# STM32.net
KiCad netlist of a schematic drawn in Altium Designer
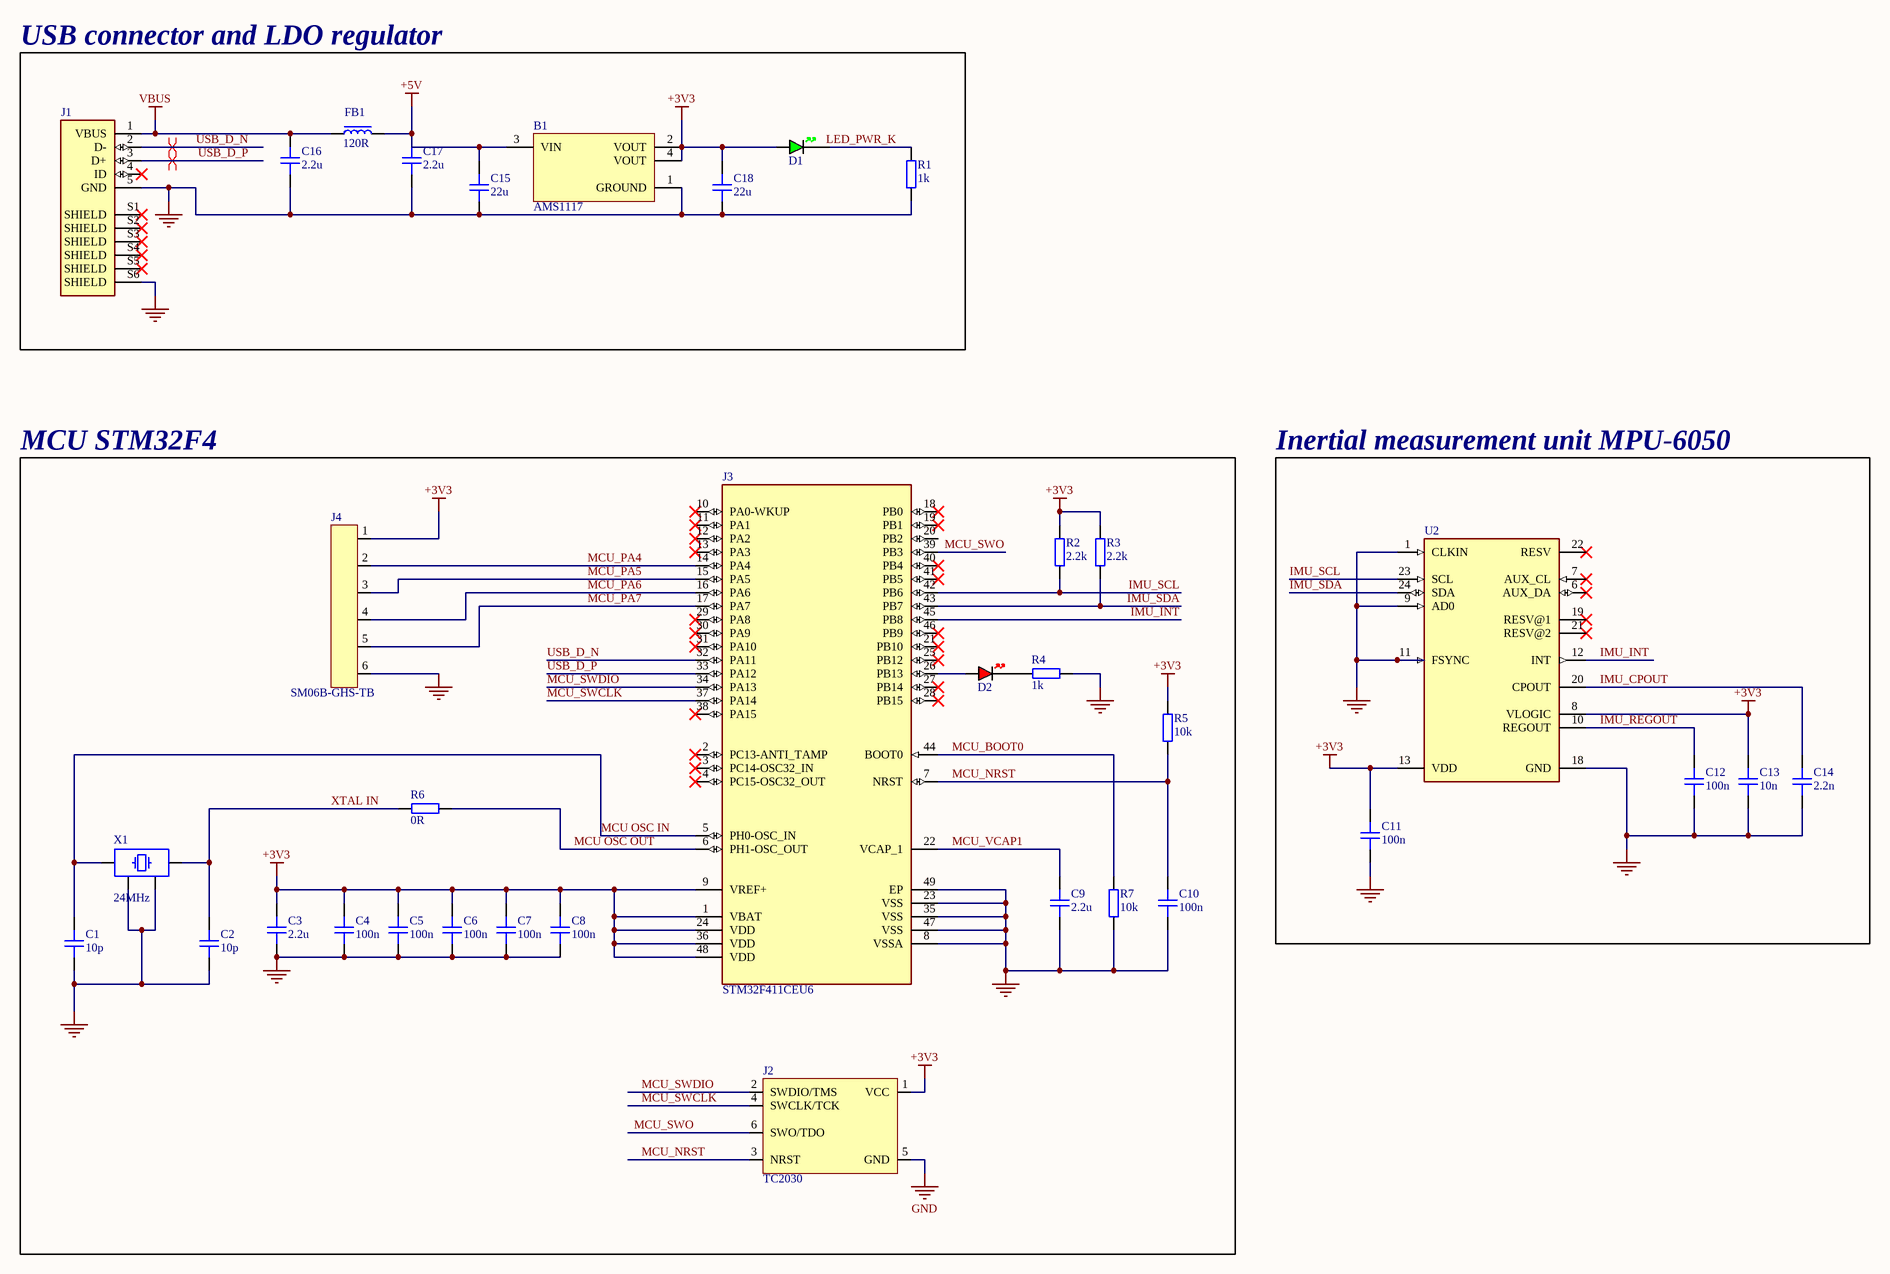
[diagram p0: STM32.SchDoc]

(export (version "E")
  (design (tool "Eeschema 10.0.6"))
  (components
    (comp (ref "B1")
      (value "AMS1117")
      (footprint "SOT229P700X180-4N")
      (description "1117")
      (libsource (lib "AMS1117") (part "AMS1117"))
    )
    (comp (ref "C1")
      (value "10p")
      (footprint "CAP_0603")
      (description "Capacitor SMD 0603")
      (libsource (lib "Schematic-Lib-PhilsLab") (part "CAP_0603"))
    )
    (comp (ref "C2")
      (value "10p")
      (footprint "CAP_0603")
      (description "Capacitor SMD 0603")
      (libsource (lib "Schematic-Lib-PhilsLab") (part "CAP_0603"))
    )
    (comp (ref "C3")
      (value "2.2u")
      (footprint "CAP_0603")
      (description "Capacitor SMD 0603")
      (libsource (lib "Schematic-Lib-PhilsLab") (part "CAP_0603"))
    )
    (comp (ref "C4")
      (value "100n")
      (footprint "CAP_0402")
      (description "Capacitor SMD 0402")
      (libsource (lib "Schematic-Lib-PhilsLab") (part "CAP_0402"))
    )
    (comp (ref "C5")
      (value "100n")
      (footprint "CAP_0402")
      (description "Capacitor SMD 0402")
      (libsource (lib "Schematic-Lib-PhilsLab") (part "CAP_0402"))
    )
    (comp (ref "C6")
      (value "100n")
      (footprint "CAP_0402")
      (description "Capacitor SMD 0402")
      (libsource (lib "Schematic-Lib-PhilsLab") (part "CAP_0402"))
    )
    (comp (ref "C7")
      (value "100n")
      (footprint "CAP_0402")
      (description "Capacitor SMD 0402")
      (libsource (lib "Schematic-Lib-PhilsLab") (part "CAP_0402"))
    )
    (comp (ref "C8")
      (value "100n")
      (footprint "CAP_0402")
      (description "Capacitor SMD 0402")
      (libsource (lib "Schematic-Lib-PhilsLab") (part "CAP_0402"))
    )
    (comp (ref "C9")
      (value "2.2u")
      (footprint "CAP_0603")
      (description "Capacitor SMD 0603")
      (libsource (lib "Schematic-Lib-PhilsLab") (part "CAP_0603"))
    )
    (comp (ref "C10")
      (value "100n")
      (footprint "CAP_0402")
      (description "Capacitor SMD 0402")
      (libsource (lib "Schematic-Lib-PhilsLab") (part "CAP_0402"))
    )
    (comp (ref "C11")
      (value "100n")
      (footprint "CAP_0402")
      (description "Capacitor SMD 0402")
      (libsource (lib "Schematic-Lib-PhilsLab") (part "CAP_0402"))
    )
    (comp (ref "C12")
      (value "100n")
      (footprint "CAP_0402")
      (description "Capacitor SMD 0402")
      (libsource (lib "Schematic-Lib-PhilsLab") (part "CAP_0402"))
    )
    (comp (ref "C13")
      (value "10n")
      (footprint "CAP_0402")
      (description "Capacitor SMD 0402")
      (libsource (lib "Schematic-Lib-PhilsLab") (part "CAP_0402"))
    )
    (comp (ref "C14")
      (value "2.2n")
      (footprint "CAP_0402")
      (description "Capacitor SMD 0402")
      (libsource (lib "Schematic-Lib-PhilsLab") (part "CAP_0402"))
    )
    (comp (ref "C15")
      (value "22u")
      (footprint "CAP_0603")
      (description "Capacitor SMD 0603")
      (libsource (lib "Schematic-Lib-PhilsLab") (part "CAP_0603"))
    )
    (comp (ref "C16")
      (value "2.2u")
      (footprint "CAP_0603")
      (description "Capacitor SMD 0603")
      (libsource (lib "Schematic-Lib-PhilsLab") (part "CAP_0603"))
    )
    (comp (ref "C17")
      (value "2.2u")
      (footprint "CAP_0603")
      (description "Capacitor SMD 0603")
      (libsource (lib "Schematic-Lib-PhilsLab") (part "CAP_0603"))
    )
    (comp (ref "C18")
      (value "22u")
      (footprint "CAP_0603")
      (description "Capacitor SMD 0603")
      (libsource (lib "Schematic-Lib-PhilsLab") (part "CAP_0603"))
    )
    (comp (ref "D1")
      (value "GREEN")
      (footprint "LED_0402_GREEN")
      (description "LED 0402 GREEN SMD")
      (libsource (lib "Schematic-Lib-PhilsLab") (part "LED_0402_GREEN"))
    )
    (comp (ref "D2")
      (value "RED")
      (footprint "LED_0402_RED")
      (description "LED 0402 RED SMD")
      (libsource (lib "Schematic-Lib-PhilsLab") (part "LED_0402_RED"))
    )
    (comp (ref "FB1")
      (value "120R")
      (footprint "FB_0603")
      (description "Ferrite Bead SMD 0603")
      (libsource (lib "Schematic-Lib-PhilsLab") (part "FB_0603"))
    )
    (comp (ref "J1")
      (value "~")
      (footprint "MOLEX_47346-0001")
      (description "USB - micro B USB 2.0 Receptacle Connector 5 Position Surface Mount, Right Angle")
      (fields (field (name "MP") "47346-0001") (field (name "MF") "Molex"))
      (libsource (lib "47346-0001") (part "47346-0001"))
    )
    (comp (ref "J2")
      (value "TC2030")
      (footprint "TC2030-FP")
      (description "Tag-Connect No-Solder SWD Debug Connector DO NOT PLACE")
      (fields (field (name "MANUFACTURER") "Tag-Connect"))
      (libsource (lib "Schematic-Lib-PhilsLab") (part "TC2030"))
    )
    (comp (ref "J3")
      (value "STM32F411CEU6")
      (footprint "QFN50P700X700X60-49N")
      (description "IC MCU 32BIT 512KB FLASH 100LQFP")
      (fields
        (field (name "MANUFACTURER") "STMicroelectronics")
        (field (name "MANUFACTURER PART NUMBER") "STM32F411VET6")
      )
      (libsource (lib "STM32") (part "STM32F411VET6"))
    )
    (comp (ref "J4")
      (value "SM06B-GHS-TB")
      (footprint "SM06B-GHS-TB")
      (description "Header Connector 6 Position 1.25MM Pitch SMD Horizontal JST GH")
      (fields (field (name "MANUFACTURER") "JST"))
      (libsource (lib "Schematic-Lib-PhilsLab") (part "SM06B-GHS-TB"))
    )
    (comp (ref "R1")
      (value "1k")
      (footprint "RES_0402")
      (description "Resistor SMD 0402")
      (libsource (lib "Schematic-Lib-PhilsLab") (part "RES_0402"))
    )
    (comp (ref "R2")
      (value "2.2k")
      (footprint "RES_0402")
      (description "Resistor SMD 0402")
      (libsource (lib "Schematic-Lib-PhilsLab") (part "RES_0402"))
    )
    (comp (ref "R3")
      (value "2.2k")
      (footprint "RES_0402")
      (description "Resistor SMD 0402")
      (libsource (lib "Schematic-Lib-PhilsLab") (part "RES_0402"))
    )
    (comp (ref "R4")
      (value "1k")
      (footprint "RES_0402")
      (description "Resistor SMD 0402")
      (libsource (lib "Schematic-Lib-PhilsLab") (part "RES_0402"))
    )
    (comp (ref "R5")
      (value "10k")
      (footprint "RES_0402")
      (description "Resistor SMD 0402")
      (libsource (lib "Schematic-Lib-PhilsLab") (part "RES_0402"))
    )
    (comp (ref "R6")
      (value "0R")
      (footprint "RES_0402")
      (description "Resistor SMD 0402")
      (libsource (lib "Schematic-Lib-PhilsLab") (part "RES_0402"))
    )
    (comp (ref "R7")
      (value "10k")
      (footprint "RES_0402")
      (description "Resistor SMD 0402")
      (libsource (lib "Schematic-Lib-PhilsLab") (part "RES_0402"))
    )
    (comp (ref "U2")
      (value "~")
      (footprint "QFN50P400X400X95-24N")
      (description "MPU-6050 series Accelerometer, Gyroscope, 3 Axis Sensor Evaluation Board")
      (fields (field (name "MF") "TDK InvenSense") (field (name "MP") "MPU-6050"))
      (libsource (lib "MPU-6050 (1)") (part "MPU-6050"))
    )
    (comp (ref "X1")
      (value "24MHz")
      (footprint "XTAL_3225")
      (description "Crystal SMD 24MHz 10PPM 7pF 3225")
      (fields
        (field (name "MANUFACTURER") "Epson")
        (field (name "MANUFACTURER PART NUMBER") "TSX-3225 24.0000MF15X-AC")
      )
      (libsource (lib "Schematic-Lib-PhilsLab") (part "TSX-3225_24.0000MF15X-AC"))
    )
  )
  (nets
    (net (code "1") (name "+3V3") (class "Default")
      (node (ref "B1") (pin "2") (pinfunction "VOUT_2") (pintype "passive"))
      (node (ref "B1") (pin "4") (pinfunction "VOUT_4") (pintype "passive"))
      (node (ref "C11") (pin "2") (pinfunction "2_2") (pintype "passive"))
      (node (ref "C13") (pin "2") (pinfunction "2_2") (pintype "passive"))
      (node (ref "C18") (pin "2") (pinfunction "2_2") (pintype "passive"))
      (node (ref "C3") (pin "2") (pinfunction "2_2") (pintype "passive"))
      (node (ref "C4") (pin "2") (pinfunction "2_2") (pintype "passive"))
      (node (ref "C5") (pin "2") (pinfunction "2_2") (pintype "passive"))
      (node (ref "C6") (pin "2") (pinfunction "2_2") (pintype "passive"))
      (node (ref "C7") (pin "2") (pinfunction "2_2") (pintype "passive"))
      (node (ref "C8") (pin "2") (pinfunction "2_2") (pintype "passive"))
      (node (ref "D1") (pin "A") (pinfunction "A_A") (pintype "passive"))
      (node (ref "J2") (pin "1") (pinfunction "VCC_1") (pintype "passive"))
      (node (ref "J3") (pin "1") (pinfunction "VBAT_1") (pintype "power_in"))
      (node (ref "J3") (pin "24") (pinfunction "VDD_24") (pintype "power_in"))
      (node (ref "J3") (pin "36") (pinfunction "VDD_36") (pintype "power_in"))
      (node (ref "J3") (pin "48") (pinfunction "VDD_48") (pintype "power_in"))
      (node (ref "J3") (pin "9") (pinfunction "VREF+_9") (pintype "power_in"))
      (node (ref "J4") (pin "1") (pinfunction "1_1") (pintype "passive"))
      (node (ref "R2") (pin "1") (pinfunction "1_1") (pintype "passive"))
      (node (ref "R3") (pin "1") (pinfunction "1_1") (pintype "passive"))
      (node (ref "R5") (pin "1") (pinfunction "1_1") (pintype "passive"))
      (node (ref "U2") (pin "13") (pinfunction "VDD_13") (pintype "power_in"))
      (node (ref "U2") (pin "8") (pinfunction "VLOGIC_8") (pintype "power_in"))
    )
    (net (code "2") (name "+5V") (class "Default")
      (node (ref "B1") (pin "3") (pinfunction "VIN_3") (pintype "passive"))
      (node (ref "C15") (pin "2") (pinfunction "2_2") (pintype "passive"))
      (node (ref "C17") (pin "2") (pinfunction "2_2") (pintype "passive"))
      (node (ref "FB1") (pin "2") (pinfunction "2_2") (pintype "passive"))
    )
    (net (code "3") (name "/IMU_CPOUT") (class "Default")
      (node (ref "C14") (pin "2") (pinfunction "2_2") (pintype "passive"))
      (node (ref "U2") (pin "20") (pinfunction "CPOUT_20") (pintype "passive"))
    )
    (net (code "4") (name "/IMU_INT") (class "Default")
      (node (ref "J3") (pin "45") (pinfunction "PB8_45") (pintype "bidirectional"))
      (node (ref "U2") (pin "12") (pinfunction "INT_12") (pintype "output"))
    )
    (net (code "5") (name "/IMU_REGOUT") (class "Default")
      (node (ref "C12") (pin "2") (pinfunction "2_2") (pintype "passive"))
      (node (ref "U2") (pin "10") (pinfunction "REGOUT_10") (pintype "passive"))
    )
    (net (code "6") (name "/IMU_SCL") (class "Default")
      (node (ref "J3") (pin "42") (pinfunction "PB6_42") (pintype "bidirectional"))
      (node (ref "R2") (pin "2") (pinfunction "2_2") (pintype "passive"))
      (node (ref "U2") (pin "23") (pinfunction "SCL_23") (pintype "input"))
    )
    (net (code "7") (name "/IMU_SDA") (class "Default")
      (node (ref "J3") (pin "43") (pinfunction "PB7_43") (pintype "bidirectional"))
      (node (ref "R3") (pin "2") (pinfunction "2_2") (pintype "passive"))
      (node (ref "U2") (pin "24") (pinfunction "SDA_24") (pintype "bidirectional"))
    )
    (net (code "8") (name "/LED_PWR_K") (class "Default")
      (node (ref "D1") (pin "K") (pinfunction "K_K") (pintype "passive"))
      (node (ref "R1") (pin "2") (pinfunction "2_2") (pintype "passive"))
    )
    (net (code "9") (name "/MCU OSC IN") (class "Default")
      (node (ref "C1") (pin "2") (pinfunction "2_2") (pintype "passive"))
      (node (ref "J3") (pin "5") (pinfunction "PH0-OSC_IN_5") (pintype "bidirectional"))
      (node (ref "X1") (pin "1") (pinfunction "1_1") (pintype "passive"))
    )
    (net (code "10") (name "/MCU OSC OUT") (class "Default")
      (node (ref "J3") (pin "6") (pinfunction "PH1-OSC_OUT_6") (pintype "bidirectional"))
      (node (ref "R6") (pin "2") (pinfunction "2_2") (pintype "passive"))
    )
    (net (code "11") (name "/MCU_BOOT0") (class "Default")
      (node (ref "J3") (pin "44") (pinfunction "BOOT0_44") (pintype "input"))
      (node (ref "R7") (pin "1") (pinfunction "1_1") (pintype "passive"))
    )
    (net (code "12") (name "/MCU_NRST") (class "Default")
      (node (ref "C10") (pin "2") (pinfunction "2_2") (pintype "passive"))
      (node (ref "J2") (pin "3") (pinfunction "NRST_3") (pintype "passive"))
      (node (ref "J3") (pin "7") (pinfunction "NRST_7") (pintype "bidirectional"))
      (node (ref "R5") (pin "2") (pinfunction "2_2") (pintype "passive"))
    )
    (net (code "13") (name "/MCU_PA4") (class "Default")
      (node (ref "J3") (pin "14") (pinfunction "PA4_14") (pintype "bidirectional"))
      (node (ref "J4") (pin "2") (pinfunction "2_2") (pintype "passive"))
    )
    (net (code "14") (name "/MCU_PA5") (class "Default")
      (node (ref "J3") (pin "15") (pinfunction "PA5_15") (pintype "bidirectional"))
      (node (ref "J4") (pin "3") (pinfunction "3_3") (pintype "passive"))
    )
    (net (code "15") (name "/MCU_PA6") (class "Default")
      (node (ref "J3") (pin "16") (pinfunction "PA6_16") (pintype "bidirectional"))
      (node (ref "J4") (pin "4") (pinfunction "4_4") (pintype "passive"))
    )
    (net (code "16") (name "/MCU_PA7") (class "Default")
      (node (ref "J3") (pin "17") (pinfunction "PA7_17") (pintype "bidirectional"))
      (node (ref "J4") (pin "5") (pinfunction "5_5") (pintype "passive"))
    )
    (net (code "17") (name "/MCU_SWCLK") (class "Default")
      (node (ref "J2") (pin "4") (pinfunction "SWCLK/TCK_4") (pintype "passive"))
      (node (ref "J3") (pin "37") (pinfunction "PA14_37") (pintype "bidirectional"))
    )
    (net (code "18") (name "/MCU_SWDIO") (class "Default")
      (node (ref "J2") (pin "2") (pinfunction "SWDIO/TMS_2") (pintype "passive"))
      (node (ref "J3") (pin "34") (pinfunction "PA13_34") (pintype "bidirectional"))
    )
    (net (code "19") (name "/MCU_SWO") (class "Default")
      (node (ref "J2") (pin "6") (pinfunction "SWO/TDO_6") (pintype "passive"))
      (node (ref "J3") (pin "39") (pinfunction "PB3_39") (pintype "bidirectional"))
    )
    (net (code "20") (name "/MCU_VCAP1") (class "Default")
      (node (ref "C9") (pin "2") (pinfunction "2_2") (pintype "passive"))
      (node (ref "J3") (pin "22") (pinfunction "VCAP_1_22") (pintype "power_in"))
    )
    (net (code "21") (name "/USB_D_N") (class "Default")
      (node (ref "J1") (pin "2") (pinfunction "D-_2") (pintype "bidirectional"))
      (node (ref "J3") (pin "32") (pinfunction "PA11_32") (pintype "bidirectional"))
    )
    (net (code "22") (name "/USB_D_P") (class "Default")
      (node (ref "J1") (pin "3") (pinfunction "D+_3") (pintype "bidirectional"))
      (node (ref "J3") (pin "33") (pinfunction "PA12_33") (pintype "bidirectional"))
    )
    (net (code "23") (name "/XTAL IN") (class "Default")
      (node (ref "C2") (pin "2") (pinfunction "2_2") (pintype "passive"))
      (node (ref "R6") (pin "1") (pinfunction "1_1") (pintype "passive"))
      (node (ref "X1") (pin "3") (pinfunction "3_3") (pintype "passive"))
    )
    (net (code "24") (name "GND") (class "Default")
      (node (ref "B1") (pin "1") (pinfunction "GROUND_1") (pintype "passive"))
      (node (ref "C1") (pin "1") (pinfunction "1_1") (pintype "passive"))
      (node (ref "C10") (pin "1") (pinfunction "1_1") (pintype "passive"))
      (node (ref "C11") (pin "1") (pinfunction "1_1") (pintype "passive"))
      (node (ref "C12") (pin "1") (pinfunction "1_1") (pintype "passive"))
      (node (ref "C13") (pin "1") (pinfunction "1_1") (pintype "passive"))
      (node (ref "C14") (pin "1") (pinfunction "1_1") (pintype "passive"))
      (node (ref "C15") (pin "1") (pinfunction "1_1") (pintype "passive"))
      (node (ref "C16") (pin "1") (pinfunction "1_1") (pintype "passive"))
      (node (ref "C17") (pin "1") (pinfunction "1_1") (pintype "passive"))
      (node (ref "C18") (pin "1") (pinfunction "1_1") (pintype "passive"))
      (node (ref "C2") (pin "1") (pinfunction "1_1") (pintype "passive"))
      (node (ref "C3") (pin "1") (pinfunction "1_1") (pintype "passive"))
      (node (ref "C4") (pin "1") (pinfunction "1_1") (pintype "passive"))
      (node (ref "C5") (pin "1") (pinfunction "1_1") (pintype "passive"))
      (node (ref "C6") (pin "1") (pinfunction "1_1") (pintype "passive"))
      (node (ref "C7") (pin "1") (pinfunction "1_1") (pintype "passive"))
      (node (ref "C8") (pin "1") (pinfunction "1_1") (pintype "passive"))
      (node (ref "C9") (pin "1") (pinfunction "1_1") (pintype "passive"))
      (node (ref "J1") (pin "5") (pinfunction "GND_5") (pintype "power_in"))
      (node (ref "J1") (pin "S6") (pinfunction "SHIELD_S6") (pintype "passive"))
      (node (ref "J2") (pin "5") (pinfunction "GND_5") (pintype "passive"))
      (node (ref "J3") (pin "23") (pinfunction "VSS_23") (pintype "power_in"))
      (node (ref "J3") (pin "35") (pinfunction "VSS_35") (pintype "power_in"))
      (node (ref "J3") (pin "47") (pinfunction "VSS_47") (pintype "power_in"))
      (node (ref "J3") (pin "49") (pinfunction "EP_49") (pintype "power_in"))
      (node (ref "J3") (pin "8") (pinfunction "VSSA_8") (pintype "power_in"))
      (node (ref "J4") (pin "6") (pinfunction "6_6") (pintype "passive"))
      (node (ref "R1") (pin "1") (pinfunction "1_1") (pintype "passive"))
      (node (ref "R4") (pin "1") (pinfunction "1_1") (pintype "passive"))
      (node (ref "R7") (pin "2") (pinfunction "2_2") (pintype "passive"))
      (node (ref "U2") (pin "1") (pinfunction "CLKIN_1") (pintype "input"))
      (node (ref "U2") (pin "11") (pinfunction "FSYNC_11") (pintype "input"))
      (node (ref "U2") (pin "18") (pinfunction "GND_18") (pintype "power_in"))
      (node (ref "U2") (pin "9") (pinfunction "AD0_9") (pintype "input"))
      (node (ref "X1") (pin "2") (pinfunction "2_2") (pintype "passive"))
      (node (ref "X1") (pin "4") (pinfunction "4_4") (pintype "passive"))
    )
    (net (code "25") (name "Net-(D2-PadK)") (class "Default")
      (node (ref "D2") (pin "K") (pinfunction "K_K") (pintype "passive"))
      (node (ref "R4") (pin "2") (pinfunction "2_2") (pintype "passive"))
    )
    (net (code "26") (name "Net-(J3-PB13)") (class "Default")
      (node (ref "D2") (pin "A") (pinfunction "A_A") (pintype "passive"))
      (node (ref "J3") (pin "26") (pinfunction "PB13_26") (pintype "bidirectional"))
    )
    (net (code "27") (name "VBUS") (class "Default")
      (node (ref "C16") (pin "2") (pinfunction "2_2") (pintype "passive"))
      (node (ref "FB1") (pin "1") (pinfunction "1_1") (pintype "passive"))
      (node (ref "J1") (pin "1") (pinfunction "VBUS_1") (pintype "power_in"))
    )
    (net (code "28") (name "unconnected-(J1-ID-Pad4)") (class "Default")
      (node (ref "J1") (pin "4") (pinfunction "ID_4") (pintype "bidirectional+no_connect"))
    )
    (net (code "29") (name "unconnected-(J1-SHIELD-PadS1)") (class "Default")
      (node (ref "J1") (pin "S1") (pinfunction "SHIELD_S1") (pintype "passive+no_connect"))
    )
    (net (code "30") (name "unconnected-(J1-SHIELD-PadS2)") (class "Default")
      (node (ref "J1") (pin "S2") (pinfunction "SHIELD_S2") (pintype "passive+no_connect"))
    )
    (net (code "31") (name "unconnected-(J1-SHIELD-PadS3)") (class "Default")
      (node (ref "J1") (pin "S3") (pinfunction "SHIELD_S3") (pintype "passive+no_connect"))
    )
    (net (code "32") (name "unconnected-(J1-SHIELD-PadS4)") (class "Default")
      (node (ref "J1") (pin "S4") (pinfunction "SHIELD_S4") (pintype "passive+no_connect"))
    )
    (net (code "33") (name "unconnected-(J1-SHIELD-PadS5)") (class "Default")
      (node (ref "J1") (pin "S5") (pinfunction "SHIELD_S5") (pintype "passive+no_connect"))
    )
    (net (code "34") (name "unconnected-(J3-PA0-WKUP-Pad10)") (class "Default")
      (node (ref "J3") (pin "10") (pinfunction "PA0-WKUP_10") (pintype "bidirectional+no_connect"))
    )
    (net (code "35") (name "unconnected-(J3-PA1-Pad11)") (class "Default")
      (node (ref "J3") (pin "11") (pinfunction "PA1_11") (pintype "bidirectional+no_connect"))
    )
    (net (code "36") (name "unconnected-(J3-PA2-Pad12)") (class "Default")
      (node (ref "J3") (pin "12") (pinfunction "PA2_12") (pintype "bidirectional+no_connect"))
    )
    (net (code "37") (name "unconnected-(J3-PA3-Pad13)") (class "Default")
      (node (ref "J3") (pin "13") (pinfunction "PA3_13") (pintype "bidirectional+no_connect"))
    )
    (net (code "38") (name "unconnected-(J3-PA8-Pad29)") (class "Default")
      (node (ref "J3") (pin "29") (pinfunction "PA8_29") (pintype "bidirectional+no_connect"))
    )
    (net (code "39") (name "unconnected-(J3-PA9-Pad30)") (class "Default")
      (node (ref "J3") (pin "30") (pinfunction "PA9_30") (pintype "bidirectional+no_connect"))
    )
    (net (code "40") (name "unconnected-(J3-PA10-Pad31)") (class "Default")
      (node (ref "J3") (pin "31") (pinfunction "PA10_31") (pintype "bidirectional+no_connect"))
    )
    (net (code "41") (name "unconnected-(J3-PA15-Pad38)") (class "Default")
      (node (ref "J3") (pin "38") (pinfunction "PA15_38") (pintype "bidirectional+no_connect"))
    )
    (net (code "42") (name "unconnected-(J3-PB0-Pad18)") (class "Default")
      (node (ref "J3") (pin "18") (pinfunction "PB0_18") (pintype "bidirectional+no_connect"))
    )
    (net (code "43") (name "unconnected-(J3-PB1-Pad19)") (class "Default")
      (node (ref "J3") (pin "19") (pinfunction "PB1_19") (pintype "bidirectional+no_connect"))
    )
    (net (code "44") (name "unconnected-(J3-PB2-Pad20)") (class "Default")
      (node (ref "J3") (pin "20") (pinfunction "PB2_20") (pintype "bidirectional"))
    )
    (net (code "45") (name "unconnected-(J3-PB4-Pad40)") (class "Default")
      (node (ref "J3") (pin "40") (pinfunction "PB4_40") (pintype "bidirectional+no_connect"))
    )
    (net (code "46") (name "unconnected-(J3-PB5-Pad41)") (class "Default")
      (node (ref "J3") (pin "41") (pinfunction "PB5_41") (pintype "bidirectional+no_connect"))
    )
    (net (code "47") (name "unconnected-(J3-PB9-Pad46)") (class "Default")
      (node (ref "J3") (pin "46") (pinfunction "PB9_46") (pintype "bidirectional+no_connect"))
    )
    (net (code "48") (name "unconnected-(J3-PB10-Pad21)") (class "Default")
      (node (ref "J3") (pin "21") (pinfunction "PB10_21") (pintype "bidirectional+no_connect"))
    )
    (net (code "49") (name "unconnected-(J3-PB12-Pad25)") (class "Default")
      (node (ref "J3") (pin "25") (pinfunction "PB12_25") (pintype "bidirectional+no_connect"))
    )
    (net (code "50") (name "unconnected-(J3-PB14-Pad27)") (class "Default")
      (node (ref "J3") (pin "27") (pinfunction "PB14_27") (pintype "bidirectional+no_connect"))
    )
    (net (code "51") (name "unconnected-(J3-PB15-Pad28)") (class "Default")
      (node (ref "J3") (pin "28") (pinfunction "PB15_28") (pintype "bidirectional+no_connect"))
    )
    (net (code "52") (name "unconnected-(J3-PC13-ANTI_TAMP-Pad2)") (class "Default")
      (node (ref "J3") (pin "2") (pinfunction "PC13-ANTI_TAMP_2") (pintype "bidirectional+no_connect"))
    )
    (net (code "53") (name "unconnected-(J3-PC14-OSC32_IN-Pad3)") (class "Default")
      (node (ref "J3") (pin "3") (pinfunction "PC14-OSC32_IN_3") (pintype "bidirectional+no_connect"))
    )
    (net (code "54") (name "unconnected-(J3-PC15-OSC32_OUT-Pad4)") (class "Default")
      (node (ref "J3") (pin "4") (pinfunction "PC15-OSC32_OUT_4") (pintype "bidirectional+no_connect"))
    )
    (net (code "55") (name "unconnected-(U2-AUX_CL-Pad7)") (class "Default")
      (node (ref "U2") (pin "7") (pinfunction "AUX_CL_7") (pintype "input+no_connect"))
    )
    (net (code "56") (name "unconnected-(U2-AUX_DA-Pad6)") (class "Default")
      (node (ref "U2") (pin "6") (pinfunction "AUX_DA_6") (pintype "bidirectional+no_connect"))
    )
    (net (code "57") (name "unconnected-(U2-RESV-Pad22)") (class "Default")
      (node (ref "U2") (pin "22") (pinfunction "RESV_22") (pintype "passive+no_connect"))
    )
    (net (code "58") (name "unconnected-(U2-RESV@1-Pad19)") (class "Default")
      (node (ref "U2") (pin "19") (pinfunction "RESV@1_19") (pintype "passive+no_connect"))
    )
    (net (code "59") (name "unconnected-(U2-RESV@2-Pad21)") (class "Default")
      (node (ref "U2") (pin "21") (pinfunction "RESV@2_21") (pintype "passive+no_connect"))
    )
  )
)
